# Y-babies_ATtiny84_v05.net
KiCad netlist of a schematic drawn in EAGLE
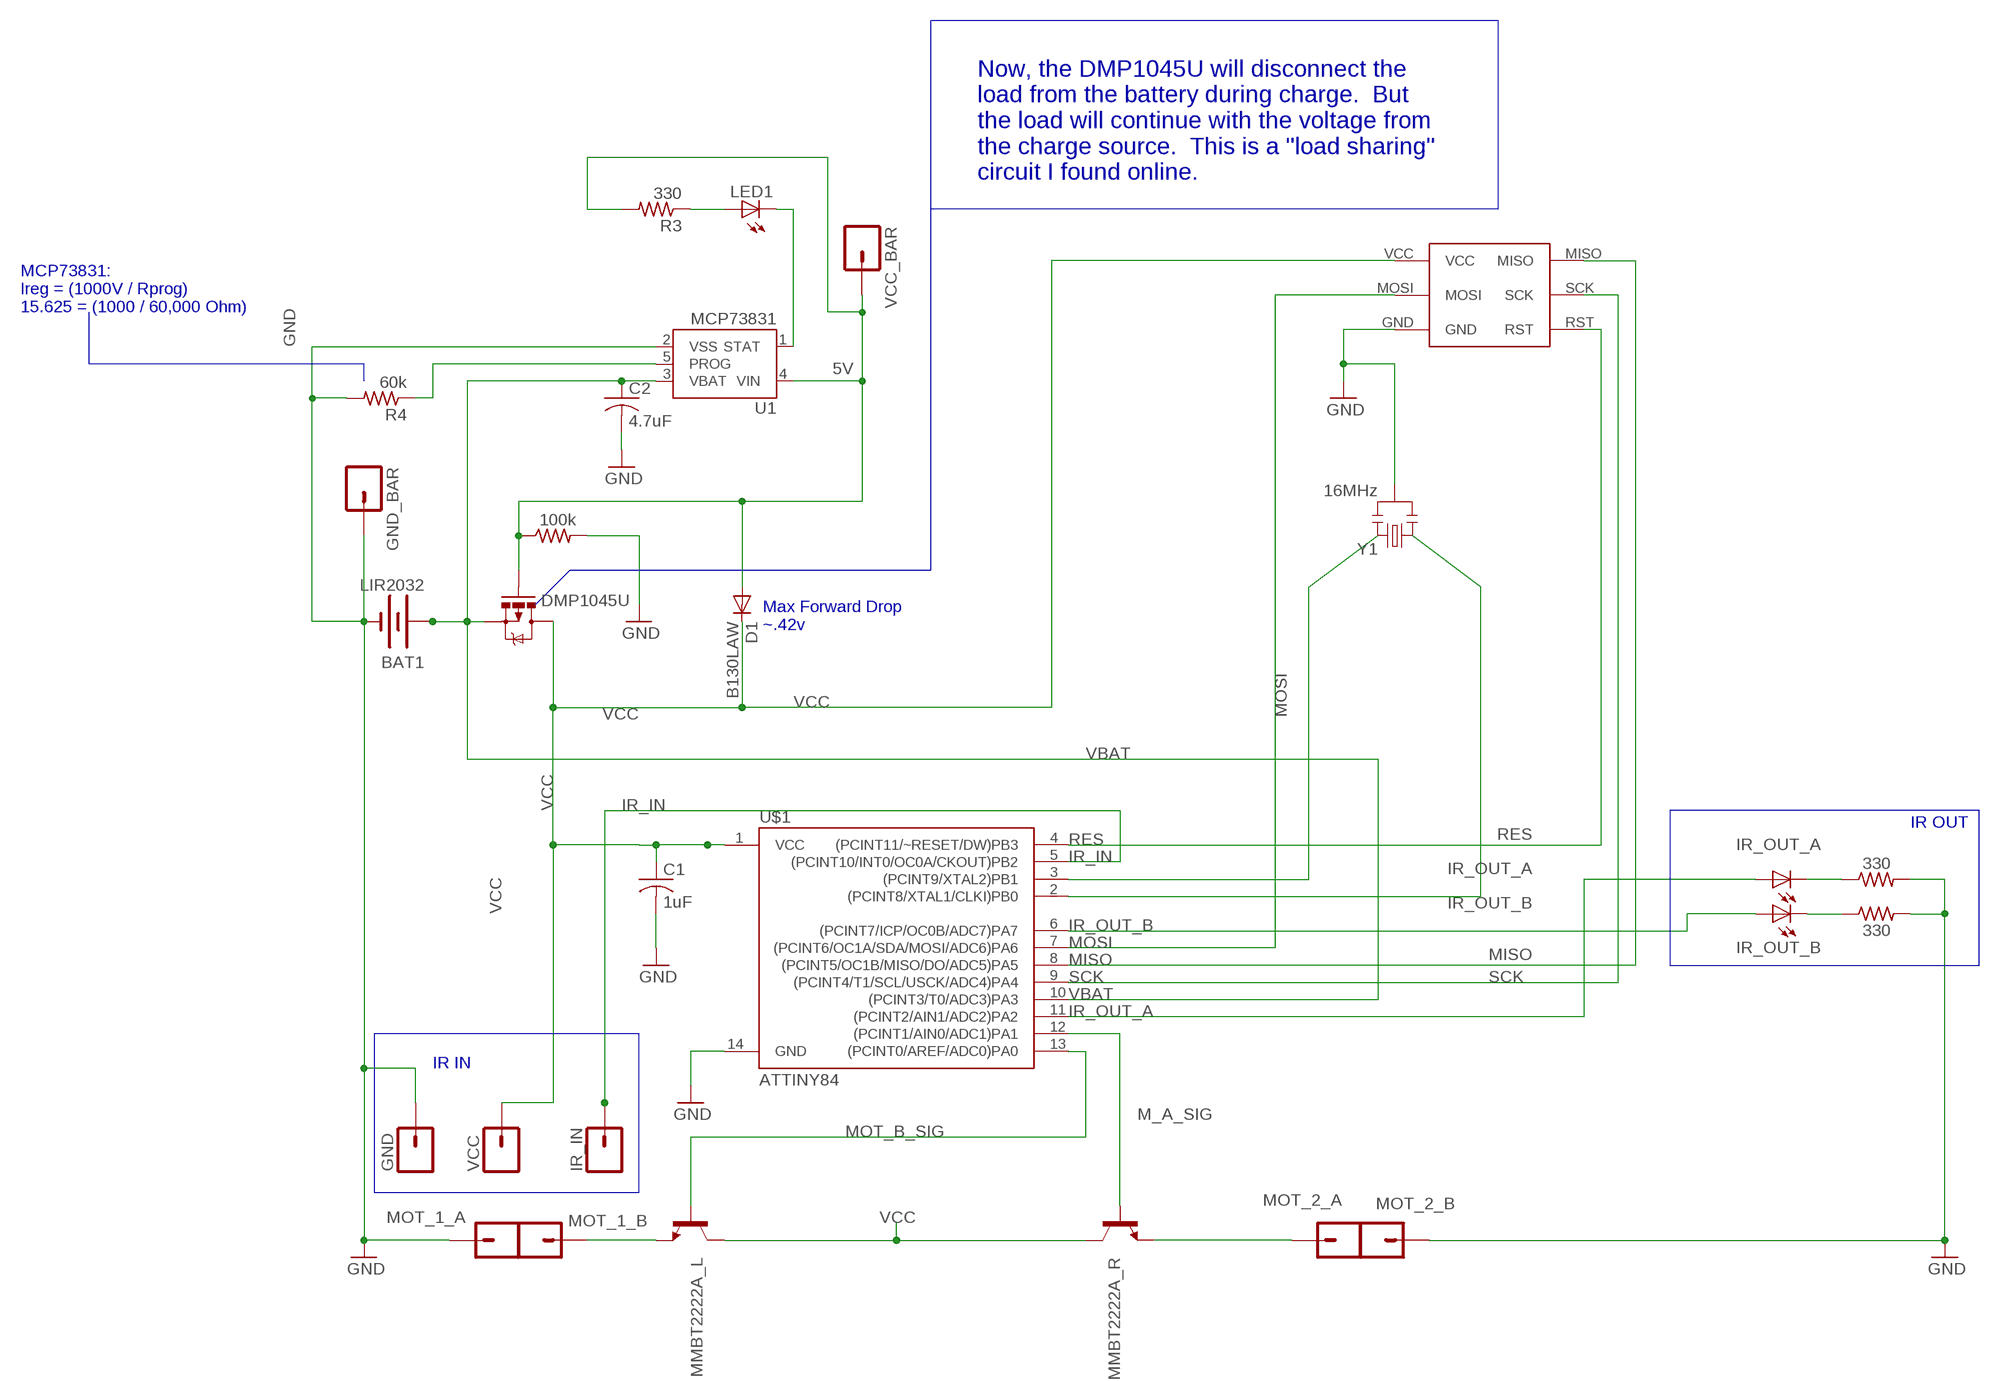
[diagram p0: schematic, sheet 1]

(export (version "E")
  (design (tool "Eeschema 10.0.6"))
  (components
    (comp (ref "BAT1")
      (value "LIR2032")
      (footprint "eagle-import:BATTCOM_20MM_PTH")
      (libsource (lib "eagle-import") (part "BATTERY20PTH"))
    )
    (comp (ref "C1")
      (value "1uF")
      (footprint "eagle-import:C0402K")
      (libsource (lib "eagle-import") (part "C-USC0402K"))
    )
    (comp (ref "C2")
      (value "4.7uF")
      (footprint "eagle-import:C0805K")
      (libsource (lib "eagle-import") (part "C-USC0805K"))
    )
    (comp (ref "D1")
      (value "B130LAW")
      (footprint "eagle-import:SOD123")
      (libsource (lib "eagle-import") (part "DIODE-SOD123"))
    )
    (comp (ref "DMP1045U")
      (value "MOSFET-PCHANNELSMD")
      (footprint "eagle-import:SOT23-3")
      (libsource (lib "eagle-import") (part "MOSFET-PCHANNELSMD"))
    )
    (comp (ref "GND")
      (value "M01PTH")
      (footprint "eagle-import:1X01")
      (libsource (lib "eagle-import") (part "M01PTH"))
    )
    (comp (ref "GND_BAR")
      (value "M01PTH")
      (footprint "eagle-import:1X01")
      (libsource (lib "eagle-import") (part "M01PTH"))
    )
    (comp (ref "IR_IN")
      (value "M01PTH")
      (footprint "eagle-import:1X01")
      (libsource (lib "eagle-import") (part "M01PTH"))
    )
    (comp (ref "IR_OUT_A")
      (value "LED3MM")
      (footprint "eagle-import:LED3MM")
      (libsource (lib "eagle-import") (part "LED3MM"))
    )
    (comp (ref "IR_OUT_B")
      (value "LED3MM")
      (footprint "eagle-import:LED3MM")
      (libsource (lib "eagle-import") (part "LED3MM"))
    )
    (comp (ref "LED1")
      (value "LEDSML0603")
      (footprint "eagle-import:SML0603")
      (libsource (lib "eagle-import") (part "LEDSML0603"))
    )
    (comp (ref "MMBT2222A_L")
      (value "TRANSISTOR_NPNSOT23")
      (footprint "eagle-import:SOT23")
      (libsource (lib "eagle-import") (part "TRANSISTOR_NPNSOT23"))
    )
    (comp (ref "MMBT2222A_R")
      (value "TRANSISTOR_NPNSOT23")
      (footprint "eagle-import:SOT23")
      (libsource (lib "eagle-import") (part "TRANSISTOR_NPNSOT23"))
    )
    (comp (ref "MOT_1_A")
      (value "M01SMD-4.5X1.5")
      (footprint "eagle-import:PAD-1.5X4.5")
      (libsource (lib "eagle-import") (part "M01SMD-4.5X1.5"))
    )
    (comp (ref "MOT_1_B")
      (value "M01SMD-4.5X1.5")
      (footprint "eagle-import:PAD-1.5X4.5")
      (libsource (lib "eagle-import") (part "M01SMD-4.5X1.5"))
    )
    (comp (ref "MOT_2_A")
      (value "M01SMD-4.5X1.5")
      (footprint "eagle-import:PAD-1.5X4.5")
      (libsource (lib "eagle-import") (part "M01SMD-4.5X1.5"))
    )
    (comp (ref "MOT_2_B")
      (value "M01SMD-4.5X1.5")
      (footprint "eagle-import:PAD-1.5X4.5")
      (libsource (lib "eagle-import") (part "M01SMD-4.5X1.5"))
    )
    (comp (ref "R1")
      (value "330")
      (footprint "eagle-import:R0402")
      (libsource (lib "eagle-import") (part "R-US_R0402"))
    )
    (comp (ref "R2")
      (value "330")
      (footprint "eagle-import:R0402")
      (libsource (lib "eagle-import") (part "R-US_R0402"))
    )
    (comp (ref "R3")
      (value "330")
      (footprint "eagle-import:R0402")
      (libsource (lib "eagle-import") (part "R-US_R0402"))
    )
    (comp (ref "R4")
      (value "60k")
      (footprint "eagle-import:R0402")
      (libsource (lib "eagle-import") (part "R-US_R0402"))
    )
    (comp (ref "R5")
      (value "100k")
      (footprint "eagle-import:R0402")
      (libsource (lib "eagle-import") (part "R-US_R0402"))
    )
    (comp (ref "U$1")
      (value "ATTINY84")
      (footprint "eagle-import:SO14")
      (libsource (lib "eagle-import") (part "ATTINY84"))
    )
    (comp (ref "U$2")
      (value "POGO_PIN_SPI_PAD")
      (footprint "eagle-import:POGO_PIN_SPI_PAD")
      (libsource (lib "eagle-import") (part "POGO_PIN_SPI_PAD"))
    )
    (comp (ref "U1")
      (value "MCP73831")
      (footprint "eagle-import:SOT23-5")
      (libsource (lib "eagle-import") (part "MCP73831"))
    )
    (comp (ref "VCC")
      (value "M01PTH")
      (footprint "eagle-import:1X01")
      (libsource (lib "eagle-import") (part "M01PTH"))
    )
    (comp (ref "VCC_BAR")
      (value "M01PTH")
      (footprint "eagle-import:1X01")
      (libsource (lib "eagle-import") (part "M01PTH"))
    )
    (comp (ref "Y1")
      (value "16MHz")
      (footprint "eagle-import:RESONATOR-SMD")
      (libsource (lib "eagle-import") (part "RESONATOR16MHZ"))
    )
  )
  (nets
    (net (code "1") (name "/5V") (class "Default")
      (node (ref "D1") (pin "A") (pinfunction "A_A") (pintype "passive"))
      (node (ref "DMP1045U") (pin "1") (pinfunction "G_1") (pintype "passive"))
      (node (ref "R3") (pin "2") (pinfunction "2_2") (pintype "passive"))
      (node (ref "R5") (pin "1") (pinfunction "1_1") (pintype "passive"))
      (node (ref "U1") (pin "4") (pinfunction "VIN_4") (pintype "power_in"))
      (node (ref "VCC_BAR") (pin "1") (pinfunction "1_1") (pintype "passive"))
    )
    (net (code "2") (name "/IR_IN") (class "Default")
      (node (ref "IR_IN") (pin "1") (pinfunction "1_1") (pintype "passive"))
      (node (ref "U$1") (pin "5") (pinfunction "(PCINT10/INT0/OC0A/CKOUT)PB2_5") (pintype "bidirectional"))
    )
    (net (code "3") (name "/IR_OUT_A") (class "Default")
      (node (ref "IR_OUT_A") (pin "A") (pinfunction "A_A") (pintype "passive"))
      (node (ref "U$1") (pin "11") (pinfunction "(PCINT2/AIN1/ADC2)PA2_11") (pintype "bidirectional"))
    )
    (net (code "4") (name "/IR_OUT_B") (class "Default")
      (node (ref "IR_OUT_B") (pin "A") (pinfunction "A_A") (pintype "passive"))
      (node (ref "U$1") (pin "6") (pinfunction "(PCINT7/ICP/OC0B/ADC7)PA7_6") (pintype "bidirectional"))
    )
    (net (code "5") (name "/MISO") (class "Default")
      (node (ref "U$1") (pin "8") (pinfunction "(PCINT5/OC1B/MISO/DO/ADC5)PA5_8") (pintype "bidirectional"))
      (node (ref "U$2") (pin "MISO") (pinfunction "MISO_MISO") (pintype "bidirectional"))
    )
    (net (code "6") (name "/MOSI") (class "Default")
      (node (ref "U$1") (pin "7") (pinfunction "(PCINT6/OC1A/SDA/MOSI/ADC6)PA6_7") (pintype "bidirectional"))
      (node (ref "U$2") (pin "MOSI") (pinfunction "MOSI_MOSI") (pintype "bidirectional"))
    )
    (net (code "7") (name "/MOT_B_SIG") (class "Default")
      (node (ref "MMBT2222A_L") (pin "1") (pinfunction "B_1") (pintype "passive"))
      (node (ref "U$1") (pin "13") (pinfunction "(PCINT0/AREF/ADC0)PA0_13") (pintype "bidirectional"))
    )
    (net (code "8") (name "/M_A_SIG") (class "Default")
      (node (ref "MMBT2222A_R") (pin "1") (pinfunction "B_1") (pintype "passive"))
      (node (ref "U$1") (pin "12") (pinfunction "(PCINT1/AIN0/ADC1)PA1_12") (pintype "bidirectional"))
    )
    (net (code "9") (name "/RES") (class "Default")
      (node (ref "U$1") (pin "4") (pinfunction "(PCINT11/~{RESET/DW})PB3_4") (pintype "bidirectional"))
      (node (ref "U$2") (pin "RST") (pinfunction "RST_RST") (pintype "bidirectional"))
    )
    (net (code "10") (name "/SCK") (class "Default")
      (node (ref "U$1") (pin "9") (pinfunction "(PCINT4/T1/SCL/USCK/ADC4)PA4_9") (pintype "bidirectional"))
      (node (ref "U$2") (pin "SCK") (pinfunction "SCK_SCK") (pintype "bidirectional"))
    )
    (net (code "11") (name "/VBAT") (class "Default")
      (node (ref "BAT1") (pin "1") (pinfunction "+_1") (pintype "power_in"))
      (node (ref "C2") (pin "1") (pinfunction "1_1") (pintype "passive"))
      (node (ref "DMP1045U") (pin "2") (pinfunction "S_2") (pintype "passive"))
      (node (ref "U$1") (pin "10") (pinfunction "(PCINT3/T0/ADC3)PA3_10") (pintype "bidirectional"))
      (node (ref "U1") (pin "3") (pinfunction "VBAT_3") (pintype "power_in"))
    )
    (net (code "12") (name "/VCC") (class "Default")
      (node (ref "C1") (pin "1") (pinfunction "1_1") (pintype "passive"))
      (node (ref "D1") (pin "C") (pinfunction "C_C") (pintype "passive"))
      (node (ref "DMP1045U") (pin "3") (pinfunction "D_3") (pintype "passive"))
      (node (ref "MMBT2222A_L") (pin "3") (pinfunction "C_3") (pintype "passive"))
      (node (ref "MMBT2222A_R") (pin "3") (pinfunction "C_3") (pintype "passive"))
      (node (ref "U$1") (pin "1") (pinfunction "VCC_1") (pintype "bidirectional"))
      (node (ref "U$2") (pin "VCC") (pinfunction "VCC_VCC") (pintype "bidirectional"))
      (node (ref "VCC") (pin "1") (pinfunction "1_1") (pintype "passive"))
    )
    (net (code "13") (name "GND") (class "Default")
      (node (ref "BAT1") (pin "2") (pinfunction "-_2") (pintype "power_in"))
      (node (ref "C1") (pin "2") (pinfunction "2_2") (pintype "passive"))
      (node (ref "C2") (pin "2") (pinfunction "2_2") (pintype "passive"))
      (node (ref "GND") (pin "1") (pinfunction "1_1") (pintype "passive"))
      (node (ref "GND_BAR") (pin "1") (pinfunction "1_1") (pintype "passive"))
      (node (ref "MOT_1_A") (pin "P$1") (pinfunction "1_P$1") (pintype "passive"))
      (node (ref "MOT_2_B") (pin "P$1") (pinfunction "1_P$1") (pintype "passive"))
      (node (ref "R1") (pin "2") (pinfunction "2_2") (pintype "passive"))
      (node (ref "R2") (pin "2") (pinfunction "2_2") (pintype "passive"))
      (node (ref "R4") (pin "2") (pinfunction "2_2") (pintype "passive"))
      (node (ref "R5") (pin "2") (pinfunction "2_2") (pintype "passive"))
      (node (ref "U$1") (pin "14") (pinfunction "GND_14") (pintype "bidirectional"))
      (node (ref "U$2") (pin "GND") (pinfunction "GND_GND") (pintype "bidirectional"))
      (node (ref "U1") (pin "2") (pinfunction "VSS_2") (pintype "power_in"))
      (node (ref "Y1") (pin "2") (pinfunction "2_2") (pintype "passive"))
    )
    (net (code "14") (name "Net-(IR_OUT_A-C)") (class "Default")
      (node (ref "IR_OUT_A") (pin "K") (pinfunction "C_K") (pintype "passive"))
      (node (ref "R1") (pin "1") (pinfunction "1_1") (pintype "passive"))
    )
    (net (code "15") (name "Net-(IR_OUT_B-C)") (class "Default")
      (node (ref "IR_OUT_B") (pin "K") (pinfunction "C_K") (pintype "passive"))
      (node (ref "R2") (pin "1") (pinfunction "1_1") (pintype "passive"))
    )
    (net (code "16") (name "Net-(LED1-PadA)") (class "Default")
      (node (ref "LED1") (pin "A") (pinfunction "A_A") (pintype "passive"))
      (node (ref "R3") (pin "1") (pinfunction "1_1") (pintype "passive"))
    )
    (net (code "17") (name "Net-(MMBT2222A_L-E)") (class "Default")
      (node (ref "MMBT2222A_L") (pin "2") (pinfunction "E_2") (pintype "passive"))
      (node (ref "MOT_1_B") (pin "P$1") (pinfunction "1_P$1") (pintype "passive"))
    )
    (net (code "18") (name "Net-(MMBT2222A_R-E)") (class "Default")
      (node (ref "MMBT2222A_R") (pin "2") (pinfunction "E_2") (pintype "passive"))
      (node (ref "MOT_2_A") (pin "P$1") (pinfunction "1_P$1") (pintype "passive"))
    )
    (net (code "19") (name "Net-(U$1-(PCINT8{slash}XTAL1{slash}CLKI)PB0)") (class "Default")
      (node (ref "U$1") (pin "2") (pinfunction "(PCINT8/XTAL1/CLKI)PB0_2") (pintype "bidirectional"))
      (node (ref "Y1") (pin "1") (pinfunction "1_1") (pintype "passive"))
    )
    (net (code "20") (name "Net-(U$1-(PCINT9{slash}XTAL2)PB1)") (class "Default")
      (node (ref "U$1") (pin "3") (pinfunction "(PCINT9/XTAL2)PB1_3") (pintype "bidirectional"))
      (node (ref "Y1") (pin "3") (pinfunction "3_3") (pintype "passive"))
    )
    (net (code "21") (name "Net-(U1-PROG)") (class "Default")
      (node (ref "R4") (pin "1") (pinfunction "1_1") (pintype "passive"))
      (node (ref "U1") (pin "5") (pinfunction "PROG_5") (pintype "input"))
    )
    (net (code "22") (name "Net-(U1-STAT)") (class "Default")
      (node (ref "LED1") (pin "C") (pinfunction "C_C") (pintype "passive"))
      (node (ref "U1") (pin "1") (pinfunction "STAT_1") (pintype "output"))
    )
  )
)
